# 5Vto3V3_v1_0.net
KiCad netlist of a schematic drawn in Altium Designer
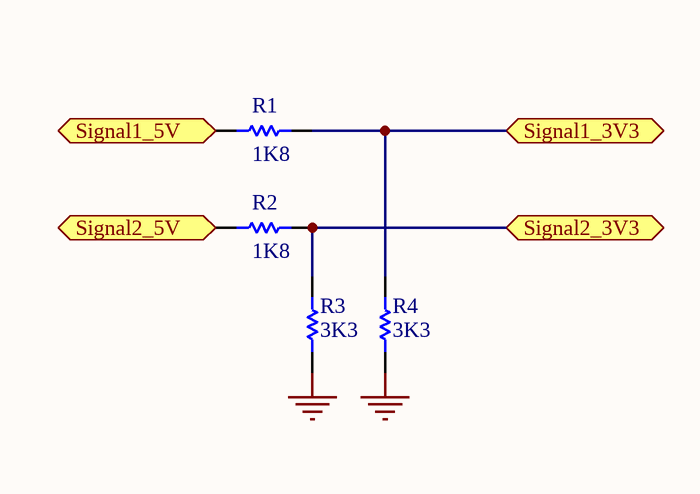
[diagram p0: 5Vto3V3_v1.0.SchDoc]

(export (version "E")
  (design (tool "Eeschema 10.0.6"))
  (components
    (comp (ref "R1")
      (value "1K8")
      (footprint "SMD_0805")
      (description "Resistor, 1/4W, 5%")
      (libsource (lib "General") (part "Resistor"))
    )
    (comp (ref "R2")
      (value "1K8")
      (footprint "SMD_0805")
      (description "Resistor, 1/4W, 5%")
      (libsource (lib "General") (part "Resistor"))
    )
    (comp (ref "R3")
      (value "3K3")
      (footprint "SMD_0805")
      (description "Resistor, 1/4W, 5%")
      (libsource (lib "General") (part "Resistor"))
    )
    (comp (ref "R4")
      (value "3K3")
      (footprint "SMD_0805")
      (description "Resistor, 1/4W, 5%")
      (libsource (lib "General") (part "Resistor"))
    )
  )
  (nets
    (net (code "1") (name "/Signal1_3V3") (class "Default")
      (node (ref "R1") (pin "2") (pinfunction "2_2") (pintype "passive"))
      (node (ref "R4") (pin "2") (pinfunction "2_2") (pintype "passive"))
    )
    (net (code "2") (name "/Signal1_5V") (class "Default")
      (node (ref "R1") (pin "1") (pinfunction "1_1") (pintype "passive"))
    )
    (net (code "3") (name "/Signal2_3V3") (class "Default")
      (node (ref "R2") (pin "2") (pinfunction "2_2") (pintype "passive"))
      (node (ref "R3") (pin "2") (pinfunction "2_2") (pintype "passive"))
    )
    (net (code "4") (name "/Signal2_5V") (class "Default")
      (node (ref "R2") (pin "1") (pinfunction "1_1") (pintype "passive"))
    )
    (net (code "5") (name "GND") (class "Default")
      (node (ref "R3") (pin "1") (pinfunction "1_1") (pintype "passive"))
      (node (ref "R4") (pin "1") (pinfunction "1_1") (pintype "passive"))
    )
  )
)
